# Acoustics_Board_Sheet_1.net
KiCad netlist of a schematic drawn in Altium Designer
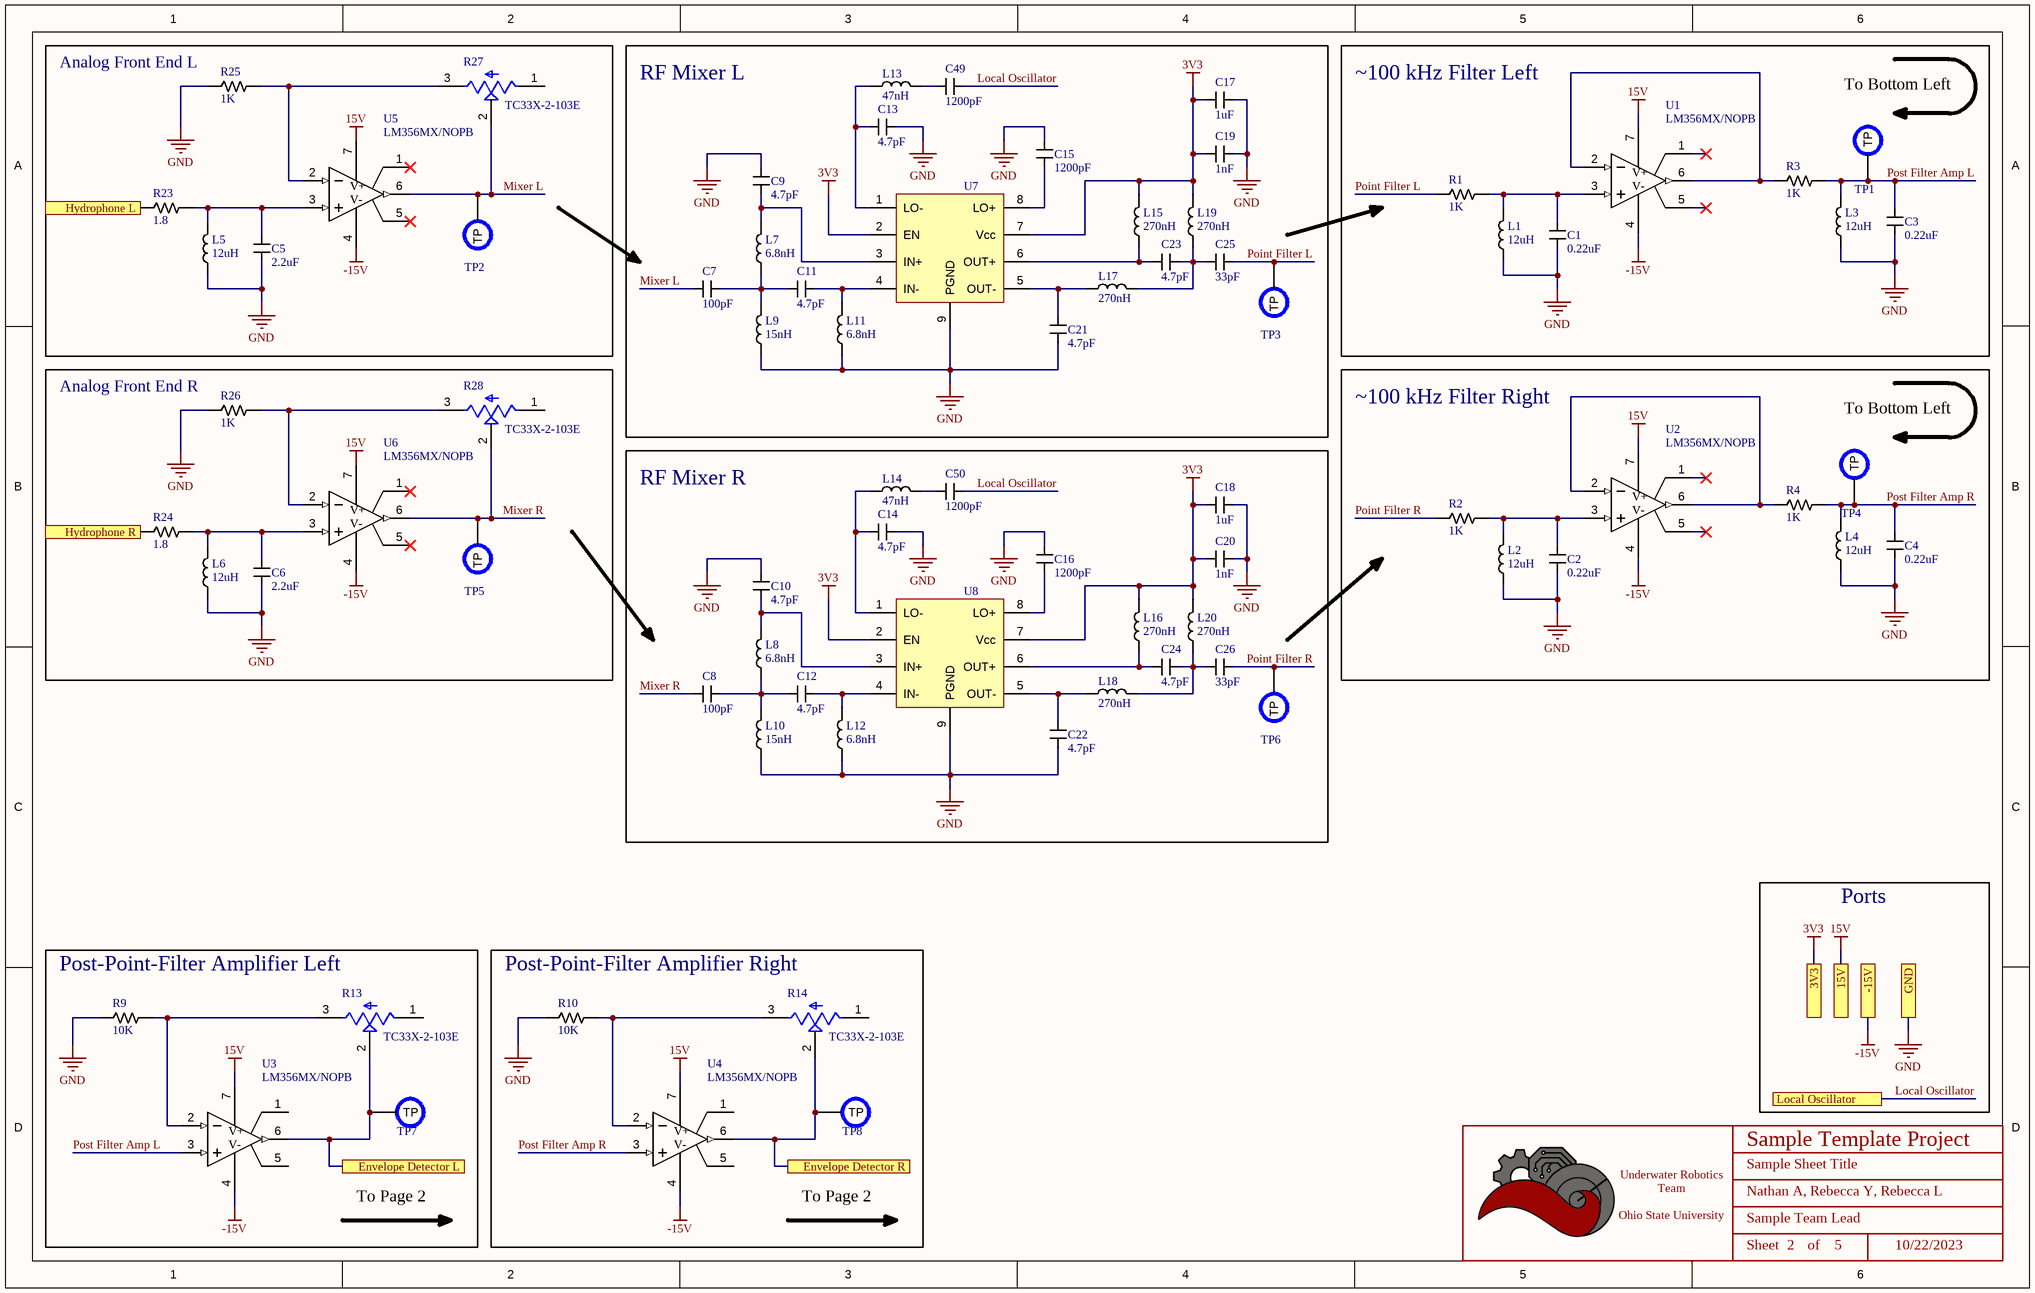
[diagram p0: Acoustics Board Sheet 1.SchDoc]

(export (version "E")
  (design (tool "Eeschema 10.0.6"))
  (components
    (comp (ref "C1")
      (value "0.22uF")
      (footprint "CAPACITOR_0603")
      (description "CAP CER 0.22uF 16V X7R 0603")
      (fields
        (field (name "TOLERANCE") "+/- 5%")
        (field (name "VOLTAGE") "16V")
        (field (name "MADE BY") "Nathan Ayer")
      )
      (libsource (lib "Capacitors") (part "CAPACITOR_0.000027uF_0603"))
    )
    (comp (ref "C2")
      (value "0.22uF")
      (footprint "CAPACITOR_0603")
      (description "CAP CER 0.22uF 16V X7R 0603")
      (fields
        (field (name "TOLERANCE") "+/- 5%")
        (field (name "VOLTAGE") "16V")
        (field (name "MADE BY") "Nathan Ayer")
      )
      (libsource (lib "Capacitors") (part "CAPACITOR_0.000027uF_0603"))
    )
    (comp (ref "C3")
      (value "0.22uF")
      (footprint "CAPACITOR_0603")
      (description "CAP CER 0.22uF 16V X7R 0603")
      (fields
        (field (name "TOLERANCE") "+/- 5%")
        (field (name "VOLTAGE") "16V")
        (field (name "MADE BY") "Nathan Ayer")
      )
      (libsource (lib "Capacitors") (part "CAPACITOR_0.000027uF_0603"))
    )
    (comp (ref "C4")
      (value "0.22uF")
      (footprint "CAPACITOR_0603")
      (description "CAP CER 0.22uF 16V X7R 0603")
      (fields
        (field (name "TOLERANCE") "+/- 5%")
        (field (name "VOLTAGE") "16V")
        (field (name "MADE BY") "Nathan Ayer")
      )
      (libsource (lib "Capacitors") (part "CAPACITOR_0.000027uF_0603"))
    )
    (comp (ref "C5")
      (value "2.2uF")
      (footprint "CAPACITOR_0603")
      (description "CAP CER 2.2PF 50V C0G/NP0 0603")
      (fields
        (field (name "TOLERANCE") "+/- 20%")
        (field (name "VOLTAGE") "6.3V")
        (field (name "MADE BY") "Flip B")
      )
      (libsource (lib "Capacitors") (part "CAPACITOR_22uF_0603"))
    )
    (comp (ref "C6")
      (value "2.2uF")
      (footprint "CAPACITOR_0603")
      (description "CAP CER 2.2PF 50V C0G/NP0 0603")
      (fields
        (field (name "TOLERANCE") "+/- 20%")
        (field (name "VOLTAGE") "6.3V")
        (field (name "MADE BY") "Flip B")
      )
      (libsource (lib "Capacitors") (part "CAPACITOR_22uF_0603"))
    )
    (comp (ref "C7")
      (value "100pF")
      (footprint "CAPACITOR_0402")
      (description "Cap 100pF 25V +/-10%\r\nCeramic 0402")
      (fields
        (field (name "TOLERANCE") "+/- 10%")
        (field (name "VOLTAGE") "25V")
        (field (name "MADE BY") "Robert Pafford")
      )
      (libsource (lib "Capacitors") (part "CAPACITOR_0.0001uF_0402"))
    )
    (comp (ref "C8")
      (value "100pF")
      (footprint "CAPACITOR_0402")
      (description "Cap 100pF 25V +/-10%\r\nCeramic 0402")
      (fields
        (field (name "TOLERANCE") "+/- 10%")
        (field (name "VOLTAGE") "25V")
        (field (name "MADE BY") "Robert Pafford")
      )
      (libsource (lib "Capacitors") (part "CAPACITOR_0.0001uF_0402"))
    )
    (comp (ref "C9")
      (value "4.7pF")
      (footprint "CAPACITOR_0402")
      (description "4.7 pF ±0.1pF 50V Ceramic Capacitor C0G, NP0 0402 (1005 Metric)")
      (fields (field (name "TOLERANCE") "+/- 0.1 pF") (field (name "VOLTAGE") "50V"))
      (libsource (lib "Capacitors") (part "CAPACITOR_0.000015uF_0402"))
    )
    (comp (ref "C10")
      (value "4.7pF")
      (footprint "CAPACITOR_0402")
      (description "4.7 pF ±0.1pF 50V Ceramic Capacitor C0G, NP0 0402 (1005 Metric)")
      (fields (field (name "TOLERANCE") "+/- 0.1 pF") (field (name "VOLTAGE") "50V"))
      (libsource (lib "Capacitors") (part "CAPACITOR_0.000015uF_0402"))
    )
    (comp (ref "C11")
      (value "4.7pF")
      (footprint "CAPACITOR_0402")
      (description "4.7 pF ±0.1pF 50V Ceramic Capacitor C0G, NP0 0402 (1005 Metric)")
      (fields (field (name "TOLERANCE") "+/- 0.1 pF") (field (name "VOLTAGE") "50V"))
      (libsource (lib "Capacitors") (part "CAPACITOR_0.000015uF_0402"))
    )
    (comp (ref "C12")
      (value "4.7pF")
      (footprint "CAPACITOR_0402")
      (description "4.7 pF ±0.1pF 50V Ceramic Capacitor C0G, NP0 0402 (1005 Metric)")
      (fields (field (name "TOLERANCE") "+/- 0.1 pF") (field (name "VOLTAGE") "50V"))
      (libsource (lib "Capacitors") (part "CAPACITOR_0.000015uF_0402"))
    )
    (comp (ref "C13")
      (value "4.7pF")
      (footprint "CAPACITOR_0402")
      (description "4.7 pF ±0.1pF 50V Ceramic Capacitor C0G, NP0 0402 (1005 Metric)")
      (fields (field (name "TOLERANCE") "+/- 0.1 pF") (field (name "VOLTAGE") "50V"))
      (libsource (lib "Capacitors") (part "CAPACITOR_0.000015uF_0402"))
    )
    (comp (ref "C14")
      (value "4.7pF")
      (footprint "CAPACITOR_0402")
      (description "4.7 pF ±0.1pF 50V Ceramic Capacitor C0G, NP0 0402 (1005 Metric)")
      (fields (field (name "TOLERANCE") "+/- 0.1 pF") (field (name "VOLTAGE") "50V"))
      (libsource (lib "Capacitors") (part "CAPACITOR_0.000015uF_0402"))
    )
    (comp (ref "C15")
      (value "1200pF")
      (footprint "CAPACITOR_0402")
      (description "CAP CER 1200PF 50V X7R 0402")
      (fields
        (field (name "TOLERANCE") "+/- 5%")
        (field (name "VOLTAGE") "50V")
        (field (name "MADE BY") "Robert Pafford")
      )
      (libsource (lib "Capacitors") (part "CAPACITOR_0.0012uF_0402"))
    )
    (comp (ref "C16")
      (value "1200pF")
      (footprint "CAPACITOR_0402")
      (description "CAP CER 1200PF 50V X7R 0402")
      (fields
        (field (name "TOLERANCE") "+/- 5%")
        (field (name "VOLTAGE") "50V")
        (field (name "MADE BY") "Robert Pafford")
      )
      (libsource (lib "Capacitors") (part "CAPACITOR_0.0012uF_0402"))
    )
    (comp (ref "C17")
      (value "1uF")
      (footprint "CAPACITOR_0603")
      (description "Cap 1uF 25V +/-10%\r\nCeramic 0603")
      (fields
        (field (name "TOLERANCE") "+/- 10%")
        (field (name "VOLTAGE") "16V")
        (field (name "MADE BY") "Flip B")
      )
      (libsource (lib "Capacitors") (part "CAPACITOR_1uF_0603_25V"))
    )
    (comp (ref "C18")
      (value "1uF")
      (footprint "CAPACITOR_0603")
      (description "Cap 1uF 25V +/-10%\r\nCeramic 0603")
      (fields
        (field (name "TOLERANCE") "+/- 10%")
        (field (name "VOLTAGE") "16V")
        (field (name "MADE BY") "Flip B")
      )
      (libsource (lib "Capacitors") (part "CAPACITOR_1uF_0603_25V"))
    )
    (comp (ref "C19")
      (value "1nF")
      (footprint "CAPACITOR_0603")
      (description "Cap 1000pF 50V +/-2%\r\nCeramic 0603")
      (fields
        (field (name "TOLERANCE") "+/- 2%")
        (field (name "VOLTAGE") "50")
        (field (name "MADE BY") "Flip B")
      )
      (libsource (lib "Capacitors") (part "CAPACITOR_0.001uF_0603"))
    )
    (comp (ref "C20")
      (value "1nF")
      (footprint "CAPACITOR_0603")
      (description "Cap 1000pF 50V +/-2%\r\nCeramic 0603")
      (fields
        (field (name "TOLERANCE") "+/- 2%")
        (field (name "VOLTAGE") "50")
        (field (name "MADE BY") "Flip B")
      )
      (libsource (lib "Capacitors") (part "CAPACITOR_0.001uF_0603"))
    )
    (comp (ref "C21")
      (value "4.7pF")
      (footprint "CAPACITOR_0402")
      (description "4.7 pF ±0.1pF 50V Ceramic Capacitor C0G, NP0 0402 (1005 Metric)")
      (fields (field (name "TOLERANCE") "+/- 0.1 pF") (field (name "VOLTAGE") "50V"))
      (libsource (lib "Capacitors") (part "CAPACITOR_0.000015uF_0402"))
    )
    (comp (ref "C22")
      (value "4.7pF")
      (footprint "CAPACITOR_0402")
      (description "4.7 pF ±0.1pF 50V Ceramic Capacitor C0G, NP0 0402 (1005 Metric)")
      (fields (field (name "TOLERANCE") "+/- 0.1 pF") (field (name "VOLTAGE") "50V"))
      (libsource (lib "Capacitors") (part "CAPACITOR_0.000015uF_0402"))
    )
    (comp (ref "C23")
      (value "4.7pF")
      (footprint "CAPACITOR_0402")
      (description "4.7 pF ±0.1pF 50V Ceramic Capacitor C0G, NP0 0402 (1005 Metric)")
      (fields (field (name "TOLERANCE") "+/- 0.1 pF") (field (name "VOLTAGE") "50V"))
      (libsource (lib "Capacitors") (part "CAPACITOR_0.000015uF_0402"))
    )
    (comp (ref "C24")
      (value "4.7pF")
      (footprint "CAPACITOR_0402")
      (description "4.7 pF ±0.1pF 50V Ceramic Capacitor C0G, NP0 0402 (1005 Metric)")
      (fields (field (name "TOLERANCE") "+/- 0.1 pF") (field (name "VOLTAGE") "50V"))
      (libsource (lib "Capacitors") (part "CAPACITOR_0.000015uF_0402"))
    )
    (comp (ref "C25")
      (value "33pF")
      (footprint "CAPACITOR_0603")
      (description "33 pF ±5% 250V Ceramic Capacitor C0G, NP0 0603 (1608 Metric)")
      (fields (field (name "TOLERANCE") "+/- 5%") (field (name "VOLTAGE") "250V"))
      (libsource (lib "Capacitors") (part "CAPACITOR_0.001uF_0603"))
    )
    (comp (ref "C26")
      (value "33pF")
      (footprint "CAPACITOR_0603")
      (description "33 pF ±5% 250V Ceramic Capacitor C0G, NP0 0603 (1608 Metric)")
      (fields (field (name "TOLERANCE") "+/- 5%") (field (name "VOLTAGE") "250V"))
      (libsource (lib "Capacitors") (part "CAPACITOR_0.001uF_0603"))
    )
    (comp (ref "C49")
      (value "1200pF")
      (footprint "CAPACITOR_0402")
      (description "CAP CER 1200PF 50V X7R 0402")
      (fields
        (field (name "TOLERANCE") "+/- 5%")
        (field (name "VOLTAGE") "50V")
        (field (name "MADE BY") "Robert Pafford")
      )
      (libsource (lib "Capacitors") (part "CAPACITOR_0.0012uF_0402"))
    )
    (comp (ref "C50")
      (value "1200pF")
      (footprint "CAPACITOR_0402")
      (description "CAP CER 1200PF 50V X7R 0402")
      (fields
        (field (name "TOLERANCE") "+/- 5%")
        (field (name "VOLTAGE") "50V")
        (field (name "MADE BY") "Robert Pafford")
      )
      (libsource (lib "Capacitors") (part "CAPACITOR_0.0012uF_0402"))
    )
    (comp (ref "L1")
      (value "12uH")
      (footprint "INDUCTOR_0603")
      (description "12 µH Shielded Multilayer Inductor 10 mA 1.8Ohm Max 0603 (1608 Metric)")
      (fields
        (field (name "TOLERANCE") "+/- 5%")
        (field (name "Comment") "FIXED IND 12UH 10MA 1.8 OHM SMD")
        (field (name "MADE BY") "Nathan Ayer")
      )
      (libsource (lib "Inductors") (part "INDUCTOR_12uH_0603"))
    )
    (comp (ref "L2")
      (value "12uH")
      (footprint "INDUCTOR_0603")
      (description "12 µH Shielded Multilayer Inductor 10 mA 1.8Ohm Max 0603 (1608 Metric)")
      (fields
        (field (name "TOLERANCE") "+/- 5%")
        (field (name "Comment") "FIXED IND 12UH 10MA 1.8 OHM SMD")
        (field (name "MADE BY") "Nathan Ayer")
      )
      (libsource (lib "Inductors") (part "INDUCTOR_12uH_0603"))
    )
    (comp (ref "L3")
      (value "12uH")
      (footprint "INDUCTOR_0603")
      (description "12 µH Shielded Multilayer Inductor 10 mA 1.8Ohm Max 0603 (1608 Metric)")
      (fields
        (field (name "TOLERANCE") "+/- 5%")
        (field (name "Comment") "FIXED IND 12UH 10MA 1.8 OHM SMD")
        (field (name "MADE BY") "Nathan Ayer")
      )
      (libsource (lib "Inductors") (part "INDUCTOR_12uH_0603"))
    )
    (comp (ref "L4")
      (value "12uH")
      (footprint "INDUCTOR_0603")
      (description "12 µH Shielded Multilayer Inductor 10 mA 1.8Ohm Max 0603 (1608 Metric)")
      (fields
        (field (name "TOLERANCE") "+/- 5%")
        (field (name "Comment") "FIXED IND 12UH 10MA 1.8 OHM SMD")
        (field (name "MADE BY") "Nathan Ayer")
      )
      (libsource (lib "Inductors") (part "INDUCTOR_12uH_0603"))
    )
    (comp (ref "L5")
      (value "12uH")
      (footprint "INDUCTOR_0603")
      (description "12 µH Shielded Multilayer Inductor 10 mA 1.8Ohm Max 0603 (1608 Metric)")
      (fields
        (field (name "TOLERANCE") "+/- 20%")
        (field (name "Comment") "FIXED IND 12UH 10MA 1.8 OHM SMD")
        (field (name "MADE BY") "Robert Pafford")
      )
      (libsource (lib "Inductors") (part "INDUCTOR_12uH_0603"))
    )
    (comp (ref "L6")
      (value "12uH")
      (footprint "INDUCTOR_0603")
      (description "12 µH Shielded Multilayer Inductor 10 mA 1.8Ohm Max 0603 (1608 Metric)")
      (fields
        (field (name "TOLERANCE") "+/- 20%")
        (field (name "Comment") "FIXED IND 12UH 10MA 1.8 OHM SMD")
        (field (name "MADE BY") "Robert Pafford")
      )
      (libsource (lib "Inductors") (part "INDUCTOR_12uH_0603"))
    )
    (comp (ref "L7")
      (value "6.8nH")
      (footprint "INDUCTOR_0402")
      (description "6.8 nH Unshielded Multilayer Inductor 250 mA 320mOhm Max 0402 (1005 Metric)")
      (fields (field (name "TOLERANCE") "+/- 5%") (field (name "Comment") "FIXED IND 6.8NH 250MA 320MOHM SM"))
      (libsource (lib "Inductors") (part "INDUCTOR_15nH_0402"))
    )
    (comp (ref "L8")
      (value "6.8nH")
      (footprint "INDUCTOR_0402")
      (description "6.8 nH Unshielded Multilayer Inductor 250 mA 320mOhm Max 0402 (1005 Metric)")
      (fields (field (name "TOLERANCE") "+/- 5%") (field (name "Comment") "FIXED IND 6.8NH 250MA 320MOHM SM"))
      (libsource (lib "Inductors") (part "INDUCTOR_15nH_0402"))
    )
    (comp (ref "L9")
      (value "15nH")
      (footprint "INDUCTOR_0402")
      (description "15 nH Unshielded Multilayer Inductor 250 mA 600mOhm Max 0402 (1005 Metric)")
      (fields (field (name "TOLERANCE") "+/- 5%") (field (name "Comment") "FIXED IND 15NH 250MA 600MOHM SMD"))
      (libsource (lib "Inductors") (part "INDUCTOR_15nH_0402"))
    )
    (comp (ref "L10")
      (value "15nH")
      (footprint "INDUCTOR_0402")
      (description "15 nH Unshielded Multilayer Inductor 250 mA 600mOhm Max 0402 (1005 Metric)")
      (fields (field (name "TOLERANCE") "+/- 5%") (field (name "Comment") "FIXED IND 15NH 250MA 600MOHM SMD"))
      (libsource (lib "Inductors") (part "INDUCTOR_15nH_0402"))
    )
    (comp (ref "L11")
      (value "6.8nH")
      (footprint "INDUCTOR_0402")
      (description "6.8 nH Unshielded Multilayer Inductor 250 mA 320mOhm Max 0402 (1005 Metric)")
      (fields (field (name "TOLERANCE") "+/- 5%") (field (name "Comment") "FIXED IND 6.8NH 250MA 320MOHM SM"))
      (libsource (lib "Inductors") (part "INDUCTOR_15nH_0402"))
    )
    (comp (ref "L12")
      (value "6.8nH")
      (footprint "INDUCTOR_0402")
      (description "6.8 nH Unshielded Multilayer Inductor 250 mA 320mOhm Max 0402 (1005 Metric)")
      (fields (field (name "TOLERANCE") "+/- 5%") (field (name "Comment") "FIXED IND 6.8NH 250MA 320MOHM SM"))
      (libsource (lib "Inductors") (part "INDUCTOR_15nH_0402"))
    )
    (comp (ref "L13")
      (value "47nH")
      (footprint "INDUCTOR_0402")
      (description "47 nH Unshielded Multilayer Inductor 200 mA 1.1Ohm Max 0402 (1005 Metric)")
      (fields (field (name "TOLERANCE") "+/- 5%") (field (name "Comment") "FIXED IND 47NH 200MA 1.1 OHM SMD"))
      (libsource (lib "Inductors") (part "INDUCTOR_15nH_0402"))
    )
    (comp (ref "L14")
      (value "47nH")
      (footprint "INDUCTOR_0402")
      (description "47 nH Unshielded Multilayer Inductor 200 mA 1.1Ohm Max 0402 (1005 Metric)")
      (fields (field (name "TOLERANCE") "+/- 5%") (field (name "Comment") "FIXED IND 47NH 200MA 1.1 OHM SMD"))
      (libsource (lib "Inductors") (part "INDUCTOR_15nH_0402"))
    )
    (comp (ref "L15")
      (value "270nH")
      (footprint "INDUCTOR_0402")
      (description "270 nH Unshielded Multilayer Inductor 110 mA 4.94Ohm Max 0402 (1005 Metric)")
      (fields
        (field (name "TOLERANCE") "+/- 10%")
        (field (name "Comment") "FIXED IND 270NH 110MA 4.94OHM SM")
      )
      (libsource (lib "Inductors") (part "INDUCTOR_15nH_0402"))
    )
    (comp (ref "L16")
      (value "270nH")
      (footprint "INDUCTOR_0402")
      (description "270 nH Unshielded Multilayer Inductor 110 mA 4.94Ohm Max 0402 (1005 Metric)")
      (fields
        (field (name "TOLERANCE") "+/- 10%")
        (field (name "Comment") "FIXED IND 270NH 110MA 4.94OHM SM")
      )
      (libsource (lib "Inductors") (part "INDUCTOR_15nH_0402"))
    )
    (comp (ref "L17")
      (value "270nH")
      (footprint "INDUCTOR_0402")
      (description "270 nH Unshielded Multilayer Inductor 110 mA 4.94Ohm Max 0402 (1005 Metric)")
      (fields
        (field (name "TOLERANCE") "+/- 10%")
        (field (name "Comment") "FIXED IND 270NH 110MA 4.94OHM SM")
      )
      (libsource (lib "Inductors") (part "INDUCTOR_15nH_0402"))
    )
    (comp (ref "L18")
      (value "270nH")
      (footprint "INDUCTOR_0402")
      (description "270 nH Unshielded Multilayer Inductor 110 mA 4.94Ohm Max 0402 (1005 Metric)")
      (fields
        (field (name "TOLERANCE") "+/- 10%")
        (field (name "Comment") "FIXED IND 270NH 110MA 4.94OHM SM")
      )
      (libsource (lib "Inductors") (part "INDUCTOR_15nH_0402"))
    )
    (comp (ref "L19")
      (value "270nH")
      (footprint "INDUCTOR_0402")
      (description "270 nH Unshielded Multilayer Inductor 110 mA 4.94Ohm Max 0402 (1005 Metric)")
      (fields
        (field (name "TOLERANCE") "+/- 10%")
        (field (name "Comment") "FIXED IND 270NH 110MA 4.94OHM SM")
      )
      (libsource (lib "Inductors") (part "INDUCTOR_15nH_0402"))
    )
    (comp (ref "L20")
      (value "270nH")
      (footprint "INDUCTOR_0402")
      (description "270 nH Unshielded Multilayer Inductor 110 mA 4.94Ohm Max 0402 (1005 Metric)")
      (fields
        (field (name "TOLERANCE") "+/- 10%")
        (field (name "Comment") "FIXED IND 270NH 110MA 4.94OHM SM")
      )
      (libsource (lib "Inductors") (part "INDUCTOR_15nH_0402"))
    )
    (comp (ref "R1")
      (value "1.45k Ohm 0.1% 1/10W")
      (footprint "RESISTOR_0603")
      (description "RES 1.45K OHM 0.1% 1/10W 0603")
      (fields
        (field (name "TOLERANCE") "+/- 0.1%")
        (field (name "VALUE  (OHMS)") "1K")
        (field (name "MADE BY") "Nathan Ayer")
      )
      (libsource (lib "Resistors") (part "RESISTOR_1K_0603"))
    )
    (comp (ref "R2")
      (value "1.45k Ohm 0.1% 1/10W")
      (footprint "RESISTOR_0603")
      (description "RES 1.45K OHM 0.1% 1/10W 0603")
      (fields
        (field (name "TOLERANCE") "+/- 0.1%")
        (field (name "VALUE  (OHMS)") "1K")
        (field (name "MADE BY") "Nathan Ayer")
      )
      (libsource (lib "Resistors") (part "RESISTOR_1K_0603"))
    )
    (comp (ref "R3")
      (value "1.45k Ohm 0.1% 1/10W")
      (footprint "RESISTOR_0603")
      (description "RES 1.45K OHM 0.1% 1/10W 0603")
      (fields
        (field (name "TOLERANCE") "+/- 0.1%")
        (field (name "VALUE  (OHMS)") "1K")
        (field (name "MADE BY") "Nathan Ayer")
      )
      (libsource (lib "Resistors") (part "RESISTOR_1K_0603"))
    )
    (comp (ref "R4")
      (value "1.45k Ohm 0.1% 1/10W")
      (footprint "RESISTOR_0603")
      (description "RES 1.45K OHM 0.1% 1/10W 0603")
      (fields
        (field (name "TOLERANCE") "+/- 0.1%")
        (field (name "VALUE  (OHMS)") "1K")
        (field (name "MADE BY") "Nathan Ayer")
      )
      (libsource (lib "Resistors") (part "RESISTOR_1K_0603"))
    )
    (comp (ref "R9")
      (value "10k Ohm 0.5% 1/10W")
      (footprint "RESISTOR_0603")
      (description "RES 10k OHM 0.5% 1/10W 0603")
      (fields
        (field (name "TOLERANCE") "+/- 0.5%")
        (field (name "VALUE  (OHMS)") "10K")
        (field (name "MADE BY") "Robert Pafford")
      )
      (libsource (lib "Resistors") (part "RESISTOR_10K_0.5%_0603"))
    )
    (comp (ref "R10")
      (value "10k Ohm 0.5% 1/10W")
      (footprint "RESISTOR_0603")
      (description "RES 10k OHM 0.5% 1/10W 0603")
      (fields
        (field (name "TOLERANCE") "+/- 0.5%")
        (field (name "VALUE  (OHMS)") "10K")
        (field (name "MADE BY") "Robert Pafford")
      )
      (libsource (lib "Resistors") (part "RESISTOR_10K_0.5%_0603"))
    )
    (comp (ref "R13")
      (value "TC33X-2-103E")
      (footprint "TRIM_TC33X-2-203E")
      (description "20 kOhms 0.1W, 1/10W J Lead Surface Mount Trimmer Potentiometer Cermet 1 Turn Top Adjustment")
      (fields (field (name "MF") "Bourns") (field (name "DIGI-KEY_PART_NUMBER") "TC33X-2-203ECT-ND"))
      (libsource (lib "Resistors") (part "TC33X-2-203E"))
    )
    (comp (ref "R14")
      (value "TC33X-2-103E")
      (footprint "TRIM_TC33X-2-203E")
      (description "20 kOhms 0.1W, 1/10W J Lead Surface Mount Trimmer Potentiometer Cermet 1 Turn Top Adjustment")
      (fields (field (name "MF") "Bourns") (field (name "DIGI-KEY_PART_NUMBER") "TC33X-2-203ECT-ND"))
      (libsource (lib "Resistors") (part "TC33X-2-203E"))
    )
    (comp (ref "R23")
      (value "2k Ohm 1% 1/16W")
      (footprint "RESISTOR_0402")
      (description "RES 2k OHM 1% 1/16W 0402")
      (fields
        (field (name "TOLERANCE") "+/- 1%")
        (field (name "VALUE  (OHMS)") "1.8")
        (field (name "MADE BY") "Flip B")
      )
      (libsource (lib "Resistors") (part "RESISTOR_2K_0402"))
    )
    (comp (ref "R24")
      (value "2k Ohm 1% 1/16W")
      (footprint "RESISTOR_0402")
      (description "RES 2k OHM 1% 1/16W 0402")
      (fields
        (field (name "TOLERANCE") "+/- 1%")
        (field (name "VALUE  (OHMS)") "1.8")
        (field (name "MADE BY") "Flip B")
      )
      (libsource (lib "Resistors") (part "RESISTOR_2K_0402"))
    )
    (comp (ref "R25")
      (value "1k Ohm 5% 1/8W")
      (footprint "RESISTOR_0603")
      (description "RES 1.8 OHM 5% 1/8W 0603")
      (fields
        (field (name "TOLERANCE") "+/- 5%")
        (field (name "VALUE  (OHMS)") "1K")
        (field (name "MADE BY") "Robert Pafford")
      )
      (libsource (lib "Resistors") (part "RESISTOR_1K_0603"))
    )
    (comp (ref "R26")
      (value "1k Ohm 5% 1/8W")
      (footprint "RESISTOR_0603")
      (description "RES 1k OHM 5% 1/8W 0603")
      (fields
        (field (name "TOLERANCE") "+/- 5%")
        (field (name "VALUE  (OHMS)") "1K")
        (field (name "MADE BY") "Robert Pafford")
      )
      (libsource (lib "Resistors") (part "RESISTOR_1K_0603"))
    )
    (comp (ref "R27")
      (value "TC33X-2-103E")
      (footprint "TRIM_TC33X-2-203E")
      (description "20 kOhms 0.1W, 1/10W J Lead Surface Mount Trimmer Potentiometer Cermet 1 Turn Top Adjustment")
      (fields (field (name "MF") "Bourns") (field (name "DIGI-KEY_PART_NUMBER") "TC33X-2-203ECT-ND"))
      (libsource (lib "Resistors") (part "TC33X-2-203E"))
    )
    (comp (ref "R28")
      (value "TC33X-2-103E")
      (footprint "TRIM_TC33X-2-203E")
      (description "20 kOhms 0.1W, 1/10W J Lead Surface Mount Trimmer Potentiometer Cermet 1 Turn Top Adjustment")
      (fields (field (name "MF") "Bourns") (field (name "DIGI-KEY_PART_NUMBER") "TC33X-2-203ECT-ND"))
      (libsource (lib "Resistors") (part "TC33X-2-203E"))
    )
    (comp (ref "TP1")
      (value "PCB Test Point")
      (footprint "TESTPOINT_1.2MM")
      (fields (field (name "MADE BY") "Robert Pafford"))
      (libsource (lib "Connectors") (part "TESTPOINT"))
    )
    (comp (ref "TP2")
      (value "PCB Test Point")
      (footprint "TESTPOINT_1.2MM")
      (fields (field (name "MADE BY") "Robert Pafford"))
      (libsource (lib "Connectors") (part "TESTPOINT"))
    )
    (comp (ref "TP3")
      (value "PCB Test Point")
      (footprint "TESTPOINT_1.2MM")
      (fields (field (name "MADE BY") "Robert Pafford"))
      (libsource (lib "Connectors") (part "TESTPOINT"))
    )
    (comp (ref "TP4")
      (value "PCB Test Point")
      (footprint "TESTPOINT_1.2MM")
      (fields (field (name "MADE BY") "Robert Pafford"))
      (libsource (lib "Connectors") (part "TESTPOINT"))
    )
    (comp (ref "TP5")
      (value "PCB Test Point")
      (footprint "TESTPOINT_1.2MM")
      (fields (field (name "MADE BY") "Robert Pafford"))
      (libsource (lib "Connectors") (part "TESTPOINT"))
    )
    (comp (ref "TP6")
      (value "PCB Test Point")
      (footprint "TESTPOINT_1.2MM")
      (fields (field (name "MADE BY") "Robert Pafford"))
      (libsource (lib "Connectors") (part "TESTPOINT"))
    )
    (comp (ref "TP7")
      (value "PCB Test Point")
      (footprint "TESTPOINT_1.2MM")
      (fields (field (name "MADE BY") "Robert Pafford"))
      (libsource (lib "Connectors") (part "TESTPOINT"))
    )
    (comp (ref "TP8")
      (value "PCB Test Point")
      (footprint "TESTPOINT_1.2MM")
      (fields (field (name "MADE BY") "Robert Pafford"))
      (libsource (lib "Connectors") (part "TESTPOINT"))
    )
    (comp (ref "U1")
      (value "LM356MX/NOPB")
      (footprint "SOIC-8")
      (description "IC OPAMP JFET 1 CIRCUIT 8SOIC")
      (fields
        (field (name "PARTNUMBER") "LM8261M5X/NOPB")
        (field (name "MANUFACTURER") "Texas Instruments")
        (field (name "CREATED BY") "Dylan T")
      )
      (libsource (lib "Integrated Circuits") (part "LM356MX/NOPB"))
    )
    (comp (ref "U2")
      (value "LM356MX/NOPB")
      (footprint "SOIC-8")
      (description "IC OPAMP JFET 1 CIRCUIT 8SOIC")
      (fields
        (field (name "PARTNUMBER") "LM8261M5X/NOPB")
        (field (name "MANUFACTURER") "Texas Instruments")
        (field (name "CREATED BY") "Dylan T")
      )
      (libsource (lib "Integrated Circuits") (part "LM356MX/NOPB"))
    )
    (comp (ref "U3")
      (value "LM356MX/NOPB")
      (footprint "SOIC-8")
      (description "IC OPAMP JFET 1 CIRCUIT 8SOIC")
      (fields
        (field (name "PARTNUMBER") "LM8261M5X/NOPB")
        (field (name "MANUFACTURER") "Texas Instruments")
        (field (name "CREATED BY") "Dylan T")
      )
      (libsource (lib "Integrated Circuits") (part "LM356MX/NOPB"))
    )
    (comp (ref "U4")
      (value "LM356MX/NOPB")
      (footprint "SOIC-8")
      (description "IC OPAMP JFET 1 CIRCUIT 8SOIC")
      (fields
        (field (name "PARTNUMBER") "LM8261M5X/NOPB")
        (field (name "MANUFACTURER") "Texas Instruments")
        (field (name "CREATED BY") "Dylan T")
      )
      (libsource (lib "Integrated Circuits") (part "LM356MX/NOPB"))
    )
    (comp (ref "U5")
      (value "LM356MX/NOPB")
      (footprint "SOIC-8")
      (description "IC OPAMP JFET 1 CIRCUIT 8SOIC")
      (fields
        (field (name "PARTNUMBER") "LM8261M5X/NOPB")
        (field (name "MANUFACTURER") "Texas Instruments")
        (field (name "CREATED BY") "Dylan T")
      )
      (libsource (lib "Integrated Circuits") (part "LM356MX/NOPB"))
    )
    (comp (ref "U6")
      (value "LM356MX/NOPB")
      (footprint "SOIC-8")
      (description "IC OPAMP JFET 1 CIRCUIT 8SOIC")
      (fields
        (field (name "PARTNUMBER") "LM8261M5X/NOPB")
        (field (name "MANUFACTURER") "Texas Instruments")
        (field (name "CREATED BY") "Dylan T")
      )
      (libsource (lib "Integrated Circuits") (part "LM356MX/NOPB"))
    )
    (comp (ref "U7")
      (value "LT5560EDD")
      (footprint "LT5560EDD")
      (description "RF Mixer IC CATV, DBS, PHS, UHF, VHF Up/Down Converter 10kHz ~ 4GHz 8-DFN (3x3)")
      (libsource (lib "Integrated Circuits") (part "LT5560EDD"))
    )
    (comp (ref "U8")
      (value "LT5560EDD")
      (footprint "LT5560EDD")
      (description "RF Mixer IC CATV, DBS, PHS, UHF, VHF Up/Down Converter 10kHz ~ 4GHz 8-DFN (3x3)")
      (libsource (lib "Integrated Circuits") (part "LT5560EDD"))
    )
  )
  (nets
    (net (code "1") (name "-15V") (class "Default")
      (node (ref "U1") (pin "4") (pinfunction "V-_4") (pintype "power_in"))
      (node (ref "U2") (pin "4") (pinfunction "V-_4") (pintype "power_in"))
      (node (ref "U3") (pin "4") (pinfunction "V-_4") (pintype "power_in"))
      (node (ref "U4") (pin "4") (pinfunction "V-_4") (pintype "power_in"))
      (node (ref "U5") (pin "4") (pinfunction "V-_4") (pintype "power_in"))
      (node (ref "U6") (pin "4") (pinfunction "V-_4") (pintype "power_in"))
    )
    (net (code "3") (name "/Envelope Detector L") (class "Default")
      (node (ref "R13") (pin "2") (pinfunction "W_2") (pintype "passive"))
      (node (ref "TP7") (pin "TP") (pinfunction "TP_TP") (pintype "passive"))
      (node (ref "U3") (pin "6") (pinfunction "OUT_6") (pintype "output"))
    )
    (net (code "4") (name "/Envelope Detector R") (class "Default")
      (node (ref "R14") (pin "2") (pinfunction "W_2") (pintype "passive"))
      (node (ref "TP8") (pin "TP") (pinfunction "TP_TP") (pintype "passive"))
      (node (ref "U4") (pin "6") (pinfunction "OUT_6") (pintype "output"))
    )
    (net (code "5") (name "/Hydrophone L") (class "Default")
      (node (ref "R23") (pin "2") (pinfunction "2_2") (pintype "passive"))
    )
    (net (code "6") (name "/Hydrophone R") (class "Default")
      (node (ref "R24") (pin "2") (pinfunction "2_2") (pintype "passive"))
    )
    (net (code "7") (name "/Local Oscillator") (class "Default")
      (node (ref "C49") (pin "1") (pinfunction "1_1") (pintype "passive"))
      (node (ref "C50") (pin "1") (pinfunction "1_1") (pintype "passive"))
    )
    (net (code "8") (name "/Mixer L") (class "Default")
      (node (ref "C7") (pin "1") (pinfunction "1_1") (pintype "passive"))
      (node (ref "R27") (pin "2") (pinfunction "W_2") (pintype "passive"))
      (node (ref "TP2") (pin "TP") (pinfunction "TP_TP") (pintype "passive"))
      (node (ref "U5") (pin "6") (pinfunction "OUT_6") (pintype "output"))
    )
    (net (code "9") (name "/Mixer R") (class "Default")
      (node (ref "C8") (pin "1") (pinfunction "1_1") (pintype "passive"))
      (node (ref "R28") (pin "2") (pinfunction "W_2") (pintype "passive"))
      (node (ref "TP5") (pin "TP") (pinfunction "TP_TP") (pintype "passive"))
      (node (ref "U6") (pin "6") (pinfunction "OUT_6") (pintype "output"))
    )
    (net (code "10") (name "/Point Filter L") (class "Default")
      (node (ref "C25") (pin "1") (pinfunction "1_1") (pintype "passive"))
      (node (ref "R1") (pin "2") (pinfunction "2_2") (pintype "passive"))
      (node (ref "TP3") (pin "TP") (pinfunction "TP_TP") (pintype "passive"))
    )
    (net (code "11") (name "/Point Filter R") (class "Default")
      (node (ref "C26") (pin "1") (pinfunction "1_1") (pintype "passive"))
      (node (ref "R2") (pin "2") (pinfunction "2_2") (pintype "passive"))
      (node (ref "TP6") (pin "TP") (pinfunction "TP_TP") (pintype "passive"))
    )
    (net (code "12") (name "/Post Filter Amp L") (class "Default")
      (node (ref "C3") (pin "1") (pinfunction "1_1") (pintype "passive"))
      (node (ref "L3") (pin "1") (pinfunction "1_1") (pintype "passive"))
      (node (ref "R3") (pin "1") (pinfunction "1_1") (pintype "passive"))
      (node (ref "TP1") (pin "TP") (pinfunction "TP_TP") (pintype "passive"))
      (node (ref "U3") (pin "3") (pinfunction "IN+_3") (pintype "input"))
    )
    (net (code "13") (name "/Post Filter Amp R") (class "Default")
      (node (ref "C4") (pin "1") (pinfunction "1_1") (pintype "passive"))
      (node (ref "L4") (pin "1") (pinfunction "1_1") (pintype "passive"))
      (node (ref "R4") (pin "1") (pinfunction "1_1") (pintype "passive"))
      (node (ref "TP4") (pin "TP") (pinfunction "TP_TP") (pintype "passive"))
      (node (ref "U4") (pin "3") (pinfunction "IN+_3") (pintype "input"))
    )
    (net (code "14") (name "3V3") (class "Default")
      (node (ref "C17") (pin "2") (pinfunction "2_2") (pintype "passive"))
      (node (ref "C18") (pin "2") (pinfunction "2_2") (pintype "passive"))
      (node (ref "C19") (pin "2") (pinfunction "2_2") (pintype "passive"))
      (node (ref "C20") (pin "2") (pinfunction "2_2") (pintype "passive"))
      (node (ref "L15") (pin "1") (pinfunction "1_1") (pintype "passive"))
      (node (ref "L16") (pin "1") (pinfunction "1_1") (pintype "passive"))
      (node (ref "L19") (pin "1") (pinfunction "1_1") (pintype "passive"))
      (node (ref "L20") (pin "1") (pinfunction "1_1") (pintype "passive"))
      (node (ref "U7") (pin "2") (pinfunction "EN_2") (pintype "passive"))
      (node (ref "U7") (pin "7") (pinfunction "Vcc_7") (pintype "passive"))
      (node (ref "U8") (pin "2") (pinfunction "EN_2") (pintype "passive"))
      (node (ref "U8") (pin "7") (pinfunction "Vcc_7") (pintype "passive"))
    )
    (net (code "15") (name "15V") (class "Default")
      (node (ref "U1") (pin "7") (pinfunction "V+_7") (pintype "power_in"))
      (node (ref "U2") (pin "7") (pinfunction "V+_7") (pintype "power_in"))
      (node (ref "U3") (pin "7") (pinfunction "V+_7") (pintype "power_in"))
      (node (ref "U4") (pin "7") (pinfunction "V+_7") (pintype "power_in"))
      (node (ref "U5") (pin "7") (pinfunction "V+_7") (pintype "power_in"))
      (node (ref "U6") (pin "7") (pinfunction "V+_7") (pintype "power_in"))
    )
    (net (code "16") (name "GND") (class "Default")
      (node (ref "C1") (pin "2") (pinfunction "2_2") (pintype "passive"))
      (node (ref "C10") (pin "1") (pinfunction "1_1") (pintype "passive"))
      (node (ref "C13") (pin "1") (pinfunction "1_1") (pintype "passive"))
      (node (ref "C14") (pin "1") (pinfunction "1_1") (pintype "passive"))
      (node (ref "C15") (pin "1") (pinfunction "1_1") (pintype "passive"))
      (node (ref "C16") (pin "1") (pinfunction "1_1") (pintype "passive"))
      (node (ref "C17") (pin "1") (pinfunction "1_1") (pintype "passive"))
      (node (ref "C18") (pin "1") (pinfunction "1_1") (pintype "passive"))
      (node (ref "C19") (pin "1") (pinfunction "1_1") (pintype "passive"))
      (node (ref "C2") (pin "2") (pinfunction "2_2") (pintype "passive"))
      (node (ref "C20") (pin "1") (pinfunction "1_1") (pintype "passive"))
      (node (ref "C21") (pin "2") (pinfunction "2_2") (pintype "passive"))
      (node (ref "C22") (pin "2") (pinfunction "2_2") (pintype "passive"))
      (node (ref "C3") (pin "2") (pinfunction "2_2") (pintype "passive"))
      (node (ref "C4") (pin "2") (pinfunction "2_2") (pintype "passive"))
      (node (ref "C5") (pin "2") (pinfunction "2_2") (pintype "passive"))
      (node (ref "C6") (pin "2") (pinfunction "2_2") (pintype "passive"))
      (node (ref "C9") (pin "1") (pinfunction "1_1") (pintype "passive"))
      (node (ref "L1") (pin "2") (pinfunction "2_2") (pintype "passive"))
      (node (ref "L10") (pin "2") (pinfunction "2_2") (pintype "passive"))
      (node (ref "L11") (pin "2") (pinfunction "2_2") (pintype "passive"))
      (node (ref "L12") (pin "2") (pinfunction "2_2") (pintype "passive"))
      (node (ref "L2") (pin "2") (pinfunction "2_2") (pintype "passive"))
      (node (ref "L3") (pin "2") (pinfunction "2_2") (pintype "passive"))
      (node (ref "L4") (pin "2") (pinfunction "2_2") (pintype "passive"))
      (node (ref "L5") (pin "2") (pinfunction "2_2") (pintype "passive"))
      (node (ref "L6") (pin "2") (pinfunction "2_2") (pintype "passive"))
      (node (ref "L9") (pin "2") (pinfunction "2_2") (pintype "passive"))
      (node (ref "R10") (pin "2") (pinfunction "2_2") (pintype "passive"))
      (node (ref "R25") (pin "2") (pinfunction "2_2") (pintype "passive"))
      (node (ref "R26") (pin "2") (pinfunction "2_2") (pintype "passive"))
      (node (ref "R9") (pin "2") (pinfunction "2_2") (pintype "passive"))
      (node (ref "U7") (pin "9") (pinfunction "PGND_9") (pintype "passive"))
      (node (ref "U8") (pin "9") (pinfunction "PGND_9") (pintype "passive"))
    )
    (net (code "17") (name "Net-(C11-Pad2)") (class "Default")
      (node (ref "C11") (pin "2") (pinfunction "2_2") (pintype "passive"))
      (node (ref "C7") (pin "2") (pinfunction "2_2") (pintype "passive"))
      (node (ref "L7") (pin "2") (pinfunction "2_2") (pintype "passive"))
      (node (ref "L9") (pin "1") (pinfunction "1_1") (pintype "passive"))
    )
    (net (code "18") (name "Net-(C12-Pad2)") (class "Default")
      (node (ref "C12") (pin "2") (pinfunction "2_2") (pintype "passive"))
      (node (ref "C8") (pin "2") (pinfunction "2_2") (pintype "passive"))
      (node (ref "L10") (pin "1") (pinfunction "1_1") (pintype "passive"))
      (node (ref "L8") (pin "2") (pinfunction "2_2") (pintype "passive"))
    )
    (net (code "19") (name "Net-(C23-Pad1)") (class "Default")
      (node (ref "C23") (pin "1") (pinfunction "1_1") (pintype "passive"))
      (node (ref "C25") (pin "2") (pinfunction "2_2") (pintype "passive"))
      (node (ref "L17") (pin "1") (pinfunction "1_1") (pintype "passive"))
      (node (ref "L19") (pin "2") (pinfunction "2_2") (pintype "passive"))
    )
    (net (code "20") (name "Net-(C24-Pad1)") (class "Default")
      (node (ref "C24") (pin "1") (pinfunction "1_1") (pintype "passive"))
      (node (ref "C26") (pin "2") (pinfunction "2_2") (pintype "passive"))
      (node (ref "L18") (pin "1") (pinfunction "1_1") (pintype "passive"))
      (node (ref "L20") (pin "2") (pinfunction "2_2") (pintype "passive"))
    )
    (net (code "21") (name "Net-(C49-Pad2)") (class "Default")
      (node (ref "C49") (pin "2") (pinfunction "2_2") (pintype "passive"))
      (node (ref "L13") (pin "1") (pinfunction "1_1") (pintype "passive"))
    )
    (net (code "22") (name "Net-(C50-Pad2)") (class "Default")
      (node (ref "C50") (pin "2") (pinfunction "2_2") (pintype "passive"))
      (node (ref "L14") (pin "1") (pinfunction "1_1") (pintype "passive"))
    )
    (net (code "23") (name "Net-(R13-CW)") (class "Default")
      (node (ref "R13") (pin "3") (pinfunction "CW_3") (pintype "passive"))
      (node (ref "R9") (pin "1") (pinfunction "1_1") (pintype "passive"))
      (node (ref "U3") (pin "2") (pinfunction "IN-_2") (pintype "input"))
    )
    (net (code "24") (name "Net-(R14-CW)") (class "Default")
      (node (ref "R10") (pin "1") (pinfunction "1_1") (pintype "passive"))
      (node (ref "R14") (pin "3") (pinfunction "CW_3") (pintype "passive"))
      (node (ref "U4") (pin "2") (pinfunction "IN-_2") (pintype "input"))
    )
    (net (code "25") (name "Net-(R27-CW)") (class "Default")
      (node (ref "R25") (pin "1") (pinfunction "1_1") (pintype "passive"))
      (node (ref "R27") (pin "3") (pinfunction "CW_3") (pintype "passive"))
      (node (ref "U5") (pin "2") (pinfunction "IN-_2") (pintype "input"))
    )
    (net (code "26") (name "Net-(R28-CW)") (class "Default")
      (node (ref "R26") (pin "1") (pinfunction "1_1") (pintype "passive"))
      (node (ref "R28") (pin "3") (pinfunction "CW_3") (pintype "passive"))
      (node (ref "U6") (pin "2") (pinfunction "IN-_2") (pintype "input"))
    )
    (net (code "27") (name "Net-(U1-IN+)") (class "Default")
      (node (ref "C1") (pin "1") (pinfunction "1_1") (pintype "passive"))
      (node (ref "L1") (pin "1") (pinfunction "1_1") (pintype "passive"))
      (node (ref "R1") (pin "1") (pinfunction "1_1") (pintype "passive"))
      (node (ref "U1") (pin "3") (pinfunction "IN+_3") (pintype "input"))
    )
    (net (code "28") (name "Net-(U1-IN-)") (class "Default")
      (node (ref "R3") (pin "2") (pinfunction "2_2") (pintype "passive"))
      (node (ref "U1") (pin "2") (pinfunction "IN-_2") (pintype "input"))
      (node (ref "U1") (pin "6") (pinfunction "OUT_6") (pintype "output"))
    )
    (net (code "29") (name "Net-(U2-IN+)") (class "Default")
      (node (ref "C2") (pin "1") (pinfunction "1_1") (pintype "passive"))
      (node (ref "L2") (pin "1") (pinfunction "1_1") (pintype "passive"))
      (node (ref "R2") (pin "1") (pinfunction "1_1") (pintype "passive"))
      (node (ref "U2") (pin "3") (pinfunction "IN+_3") (pintype "input"))
    )
    (net (code "30") (name "Net-(U2-IN-)") (class "Default")
      (node (ref "R4") (pin "2") (pinfunction "2_2") (pintype "passive"))
      (node (ref "U2") (pin "2") (pinfunction "IN-_2") (pintype "input"))
      (node (ref "U2") (pin "6") (pinfunction "OUT_6") (pintype "output"))
    )
    (net (code "31") (name "Net-(U5-IN+)") (class "Default")
      (node (ref "C5") (pin "1") (pinfunction "1_1") (pintype "passive"))
      (node (ref "L5") (pin "1") (pinfunction "1_1") (pintype "passive"))
      (node (ref "R23") (pin "1") (pinfunction "1_1") (pintype "passive"))
      (node (ref "U5") (pin "3") (pinfunction "IN+_3") (pintype "input"))
    )
    (net (code "32") (name "Net-(U6-IN+)") (class "Default")
      (node (ref "C6") (pin "1") (pinfunction "1_1") (pintype "passive"))
      (node (ref "L6") (pin "1") (pinfunction "1_1") (pintype "passive"))
      (node (ref "R24") (pin "1") (pinfunction "1_1") (pintype "passive"))
      (node (ref "U6") (pin "3") (pinfunction "IN+_3") (pintype "input"))
    )
    (net (code "33") (name "Net-(U7-IN+)") (class "Default")
      (node (ref "C9") (pin "2") (pinfunction "2_2") (pintype "passive"))
      (node (ref "L7") (pin "1") (pinfunction "1_1") (pintype "passive"))
      (node (ref "U7") (pin "3") (pinfunction "IN+_3") (pintype "passive"))
    )
    (net (code "34") (name "Net-(U7-IN-)") (class "Default")
      (node (ref "C11") (pin "1") (pinfunction "1_1") (pintype "passive"))
      (node (ref "L11") (pin "1") (pinfunction "1_1") (pintype "passive"))
      (node (ref "U7") (pin "4") (pinfunction "IN-_4") (pintype "passive"))
    )
    (net (code "35") (name "Net-(U7-LO+)") (class "Default")
      (node (ref "C15") (pin "2") (pinfunction "2_2") (pintype "passive"))
      (node (ref "U7") (pin "8") (pinfunction "LO+_8") (pintype "passive"))
    )
    (net (code "36") (name "Net-(U7-LO-)") (class "Default")
      (node (ref "C13") (pin "2") (pinfunction "2_2") (pintype "passive"))
      (node (ref "L13") (pin "2") (pinfunction "2_2") (pintype "passive"))
      (node (ref "U7") (pin "1") (pinfunction "LO-_1") (pintype "passive"))
    )
    (net (code "37") (name "Net-(U7-OUT+)") (class "Default")
      (node (ref "C23") (pin "2") (pinfunction "2_2") (pintype "passive"))
      (node (ref "L15") (pin "2") (pinfunction "2_2") (pintype "passive"))
      (node (ref "U7") (pin "6") (pinfunction "OUT+_6") (pintype "passive"))
    )
    (net (code "38") (name "Net-(U7-OUT-)") (class "Default")
      (node (ref "C21") (pin "1") (pinfunction "1_1") (pintype "passive"))
      (node (ref "L17") (pin "2") (pinfunction "2_2") (pintype "passive"))
      (node (ref "U7") (pin "5") (pinfunction "OUT-_5") (pintype "passive"))
    )
    (net (code "39") (name "Net-(U8-IN+)") (class "Default")
      (node (ref "C10") (pin "2") (pinfunction "2_2") (pintype "passive"))
      (node (ref "L8") (pin "1") (pinfunction "1_1") (pintype "passive"))
      (node (ref "U8") (pin "3") (pinfunction "IN+_3") (pintype "passive"))
    )
    (net (code "40") (name "Net-(U8-IN-)") (class "Default")
      (node (ref "C12") (pin "1") (pinfunction "1_1") (pintype "passive"))
      (node (ref "L12") (pin "1") (pinfunction "1_1") (pintype "passive"))
      (node (ref "U8") (pin "4") (pinfunction "IN-_4") (pintype "passive"))
    )
    (net (code "41") (name "Net-(U8-LO+)") (class "Default")
      (node (ref "C16") (pin "2") (pinfunction "2_2") (pintype "passive"))
      (node (ref "U8") (pin "8") (pinfunction "LO+_8") (pintype "passive"))
    )
    (net (code "42") (name "Net-(U8-LO-)") (class "Default")
      (node (ref "C14") (pin "2") (pinfunction "2_2") (pintype "passive"))
      (node (ref "L14") (pin "2") (pinfunction "2_2") (pintype "passive"))
      (node (ref "U8") (pin "1") (pinfunction "LO-_1") (pintype "passive"))
    )
    (net (code "43") (name "Net-(U8-OUT+)") (class "Default")
      (node (ref "C24") (pin "2") (pinfunction "2_2") (pintype "passive"))
      (node (ref "L16") (pin "2") (pinfunction "2_2") (pintype "passive"))
      (node (ref "U8") (pin "6") (pinfunction "OUT+_6") (pintype "passive"))
    )
    (net (code "44") (name "Net-(U8-OUT-)") (class "Default")
      (node (ref "C22") (pin "1") (pinfunction "1_1") (pintype "passive"))
      (node (ref "L18") (pin "2") (pinfunction "2_2") (pintype "passive"))
      (node (ref "U8") (pin "5") (pinfunction "OUT-_5") (pintype "passive"))
    )
    (net (code "45") (name "unconnected-(R13-CCW-Pad1)") (class "Default")
      (node (ref "R13") (pin "1") (pinfunction "CCW_1") (pintype "passive"))
    )
    (net (code "46") (name "unconnected-(R14-CCW-Pad1)") (class "Default")
      (node (ref "R14") (pin "1") (pinfunction "CCW_1") (pintype "passive"))
    )
    (net (code "47") (name "unconnected-(R27-CCW-Pad1)") (class "Default")
      (node (ref "R27") (pin "1") (pinfunction "CCW_1") (pintype "passive"))
    )
    (net (code "48") (name "unconnected-(R28-CCW-Pad1)") (class "Default")
      (node (ref "R28") (pin "1") (pinfunction "CCW_1") (pintype "passive"))
    )
    (net (code "49") (name "unconnected-(U1-Balance-Pad1)") (class "Default")
      (node (ref "U1") (pin "1") (pinfunction "Balance_1") (pintype "passive+no_connect"))
    )
    (net (code "50") (name "unconnected-(U1-Balance-Pad5)") (class "Default")
      (node (ref "U1") (pin "5") (pinfunction "Balance_5") (pintype "passive+no_connect"))
    )
    (net (code "51") (name "unconnected-(U2-Balance-Pad1)") (class "Default")
      (node (ref "U2") (pin "1") (pinfunction "Balance_1") (pintype "passive+no_connect"))
    )
    (net (code "52") (name "unconnected-(U2-Balance-Pad5)") (class "Default")
      (node (ref "U2") (pin "5") (pinfunction "Balance_5") (pintype "passive+no_connect"))
    )
    (net (code "53") (name "unconnected-(U3-Balance-Pad1)") (class "Default")
      (node (ref "U3") (pin "1") (pinfunction "Balance_1") (pintype "passive"))
    )
    (net (code "54") (name "unconnected-(U3-Balance-Pad5)") (class "Default")
      (node (ref "U3") (pin "5") (pinfunction "Balance_5") (pintype "passive"))
    )
    (net (code "55") (name "unconnected-(U4-Balance-Pad1)") (class "Default")
      (node (ref "U4") (pin "1") (pinfunction "Balance_1") (pintype "passive"))
    )
    (net (code "56") (name "unconnected-(U4-Balance-Pad5)") (class "Default")
      (node (ref "U4") (pin "5") (pinfunction "Balance_5") (pintype "passive"))
    )
    (net (code "57") (name "unconnected-(U5-Balance-Pad1)") (class "Default")
      (node (ref "U5") (pin "1") (pinfunction "Balance_1") (pintype "passive+no_connect"))
    )
    (net (code "58") (name "unconnected-(U5-Balance-Pad5)") (class "Default")
      (node (ref "U5") (pin "5") (pinfunction "Balance_5") (pintype "passive+no_connect"))
    )
    (net (code "59") (name "unconnected-(U6-Balance-Pad1)") (class "Default")
      (node (ref "U6") (pin "1") (pinfunction "Balance_1") (pintype "passive+no_connect"))
    )
    (net (code "60") (name "unconnected-(U6-Balance-Pad5)") (class "Default")
      (node (ref "U6") (pin "5") (pinfunction "Balance_5") (pintype "passive+no_connect"))
    )
  )
)
